# logicka_sonda.net
KiCad netlist of a schematic drawn in EAGLE
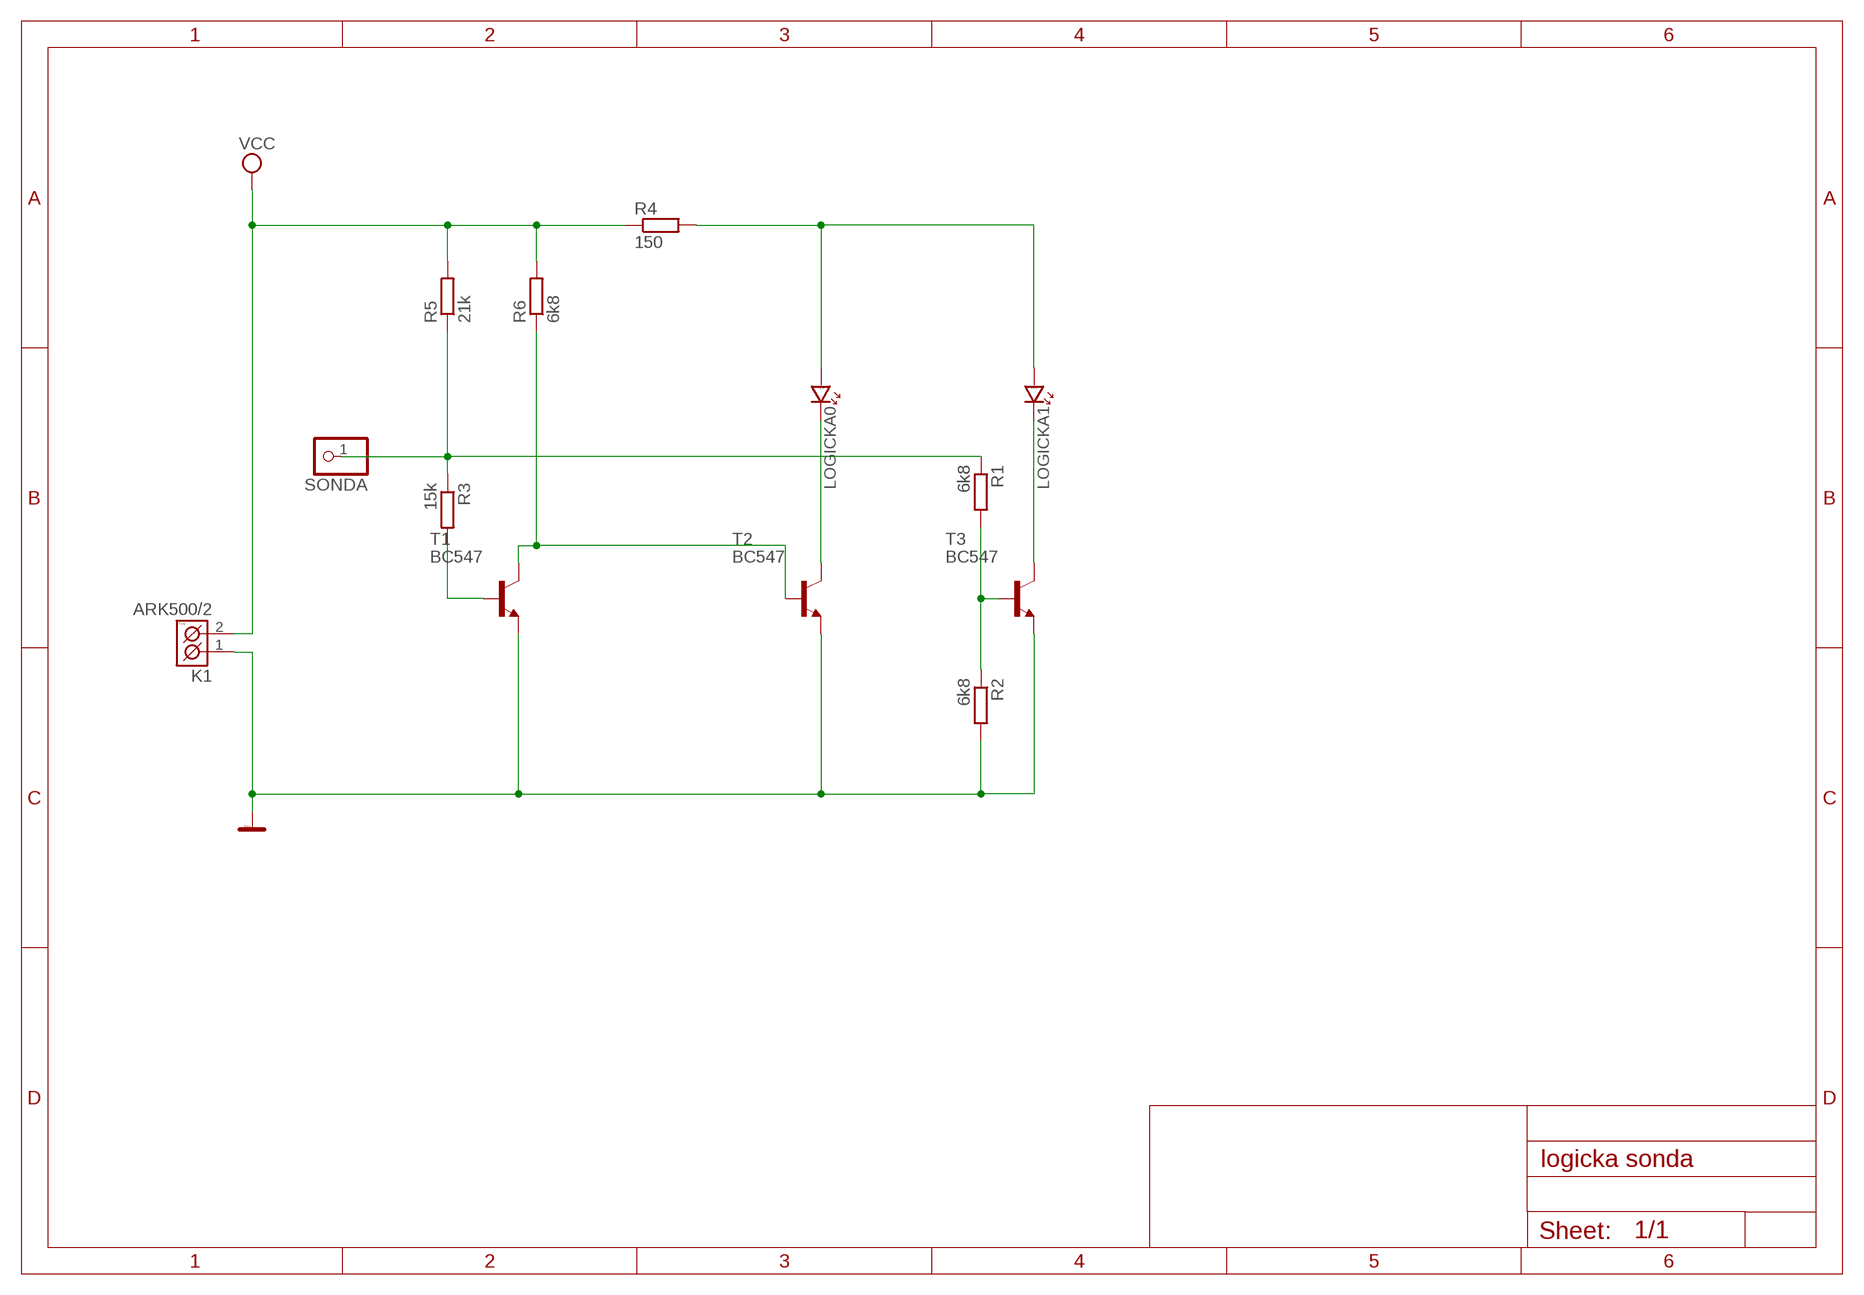
[diagram p0: schematic, sheet 1]

(export (version "E")
  (design (tool "Eeschema 10.0.6"))
  (components
    (comp (ref "K1")
      (value "ARK500/2")
      (footprint "eagle-import:ARK500_2")
      (libsource (lib "eagle-import") (part "ARK500/2"))
    )
    (comp (ref "LOGICKA0")
      (value "LED_5")
      (footprint "eagle-import:LED_5")
      (libsource (lib "eagle-import") (part "LED_5"))
    )
    (comp (ref "LOGICKA1")
      (value "LED_5")
      (footprint "eagle-import:LED_5")
      (libsource (lib "eagle-import") (part "LED_5"))
    )
    (comp (ref "R1")
      (value "6k8")
      (footprint "eagle-import:0207_10")
      (libsource (lib "eagle-import") (part "R-EU_0207/10"))
    )
    (comp (ref "R2")
      (value "6k8")
      (footprint "eagle-import:0207_10")
      (libsource (lib "eagle-import") (part "R-EU_0207/10"))
    )
    (comp (ref "R3")
      (value "15k")
      (footprint "eagle-import:0207_10")
      (libsource (lib "eagle-import") (part "R-EU_0207/10"))
    )
    (comp (ref "R4")
      (value "150")
      (footprint "eagle-import:0207_10")
      (libsource (lib "eagle-import") (part "R-EU_0207/10"))
    )
    (comp (ref "R5")
      (value "21k")
      (footprint "eagle-import:0207_10")
      (libsource (lib "eagle-import") (part "R-EU_0207/10"))
    )
    (comp (ref "R6")
      (value "6k8")
      (footprint "eagle-import:0207_10")
      (libsource (lib "eagle-import") (part "R-EU_0207/10"))
    )
    (comp (ref "SONDA")
      (value "PINHD-1X1")
      (footprint "eagle-import:1X01")
      (libsource (lib "eagle-import") (part "PINHD-1X1"))
    )
    (comp (ref "T1")
      (value "BC547")
      (footprint "eagle-import:TO92")
      (libsource (lib "eagle-import") (part "BC547"))
    )
    (comp (ref "T2")
      (value "BC547")
      (footprint "eagle-import:TO92")
      (libsource (lib "eagle-import") (part "BC547"))
    )
    (comp (ref "T3")
      (value "BC547")
      (footprint "eagle-import:TO92")
      (libsource (lib "eagle-import") (part "BC547"))
    )
  )
  (nets
    (net (code "1") (name "GND") (class "Default")
      (node (ref "K1") (pin "1") (pinfunction "K1_1") (pintype "passive"))
      (node (ref "R2") (pin "2") (pinfunction "2_2") (pintype "passive"))
      (node (ref "T1") (pin "1") (pinfunction "E_1") (pintype "passive"))
      (node (ref "T2") (pin "1") (pinfunction "E_1") (pintype "passive"))
      (node (ref "T3") (pin "1") (pinfunction "E_1") (pintype "passive"))
    )
    (net (code "2") (name "Net-(LOGICKA0-PadA)") (class "Default")
      (node (ref "LOGICKA0") (pin "A") (pinfunction "A_A") (pintype "passive"))
      (node (ref "LOGICKA1") (pin "A") (pinfunction "A_A") (pintype "passive"))
      (node (ref "R4") (pin "2") (pinfunction "2_2") (pintype "passive"))
    )
    (net (code "3") (name "Net-(R1-Pad1)") (class "Default")
      (node (ref "R1") (pin "1") (pinfunction "1_1") (pintype "passive"))
      (node (ref "R3") (pin "1") (pinfunction "1_1") (pintype "passive"))
      (node (ref "R5") (pin "1") (pinfunction "1_1") (pintype "passive"))
      (node (ref "SONDA") (pin "1") (pinfunction "1_1") (pintype "passive"))
    )
    (net (code "4") (name "Net-(T1-B)") (class "Default")
      (node (ref "R3") (pin "2") (pinfunction "2_2") (pintype "passive"))
      (node (ref "T1") (pin "2") (pinfunction "B_2") (pintype "passive"))
    )
    (net (code "5") (name "Net-(T1-C)") (class "Default")
      (node (ref "R6") (pin "1") (pinfunction "1_1") (pintype "passive"))
      (node (ref "T1") (pin "3") (pinfunction "C_3") (pintype "passive"))
      (node (ref "T2") (pin "2") (pinfunction "B_2") (pintype "passive"))
    )
    (net (code "6") (name "Net-(T2-C)") (class "Default")
      (node (ref "LOGICKA0") (pin "K") (pinfunction "K_K") (pintype "passive"))
      (node (ref "T2") (pin "3") (pinfunction "C_3") (pintype "passive"))
    )
    (net (code "7") (name "Net-(T3-B)") (class "Default")
      (node (ref "R1") (pin "2") (pinfunction "2_2") (pintype "passive"))
      (node (ref "R2") (pin "1") (pinfunction "1_1") (pintype "passive"))
      (node (ref "T3") (pin "2") (pinfunction "B_2") (pintype "passive"))
    )
    (net (code "8") (name "Net-(T3-C)") (class "Default")
      (node (ref "LOGICKA1") (pin "K") (pinfunction "K_K") (pintype "passive"))
      (node (ref "T3") (pin "3") (pinfunction "C_3") (pintype "passive"))
    )
    (net (code "9") (name "VCC") (class "Default")
      (node (ref "K1") (pin "2") (pinfunction "K2_2") (pintype "passive"))
      (node (ref "R4") (pin "1") (pinfunction "1_1") (pintype "passive"))
      (node (ref "R5") (pin "2") (pinfunction "2_2") (pintype "passive"))
      (node (ref "R6") (pin "2") (pinfunction "2_2") (pintype "passive"))
    )
  )
)
